# COMMUNICATION.net
KiCad netlist of a schematic drawn in Altium Designer
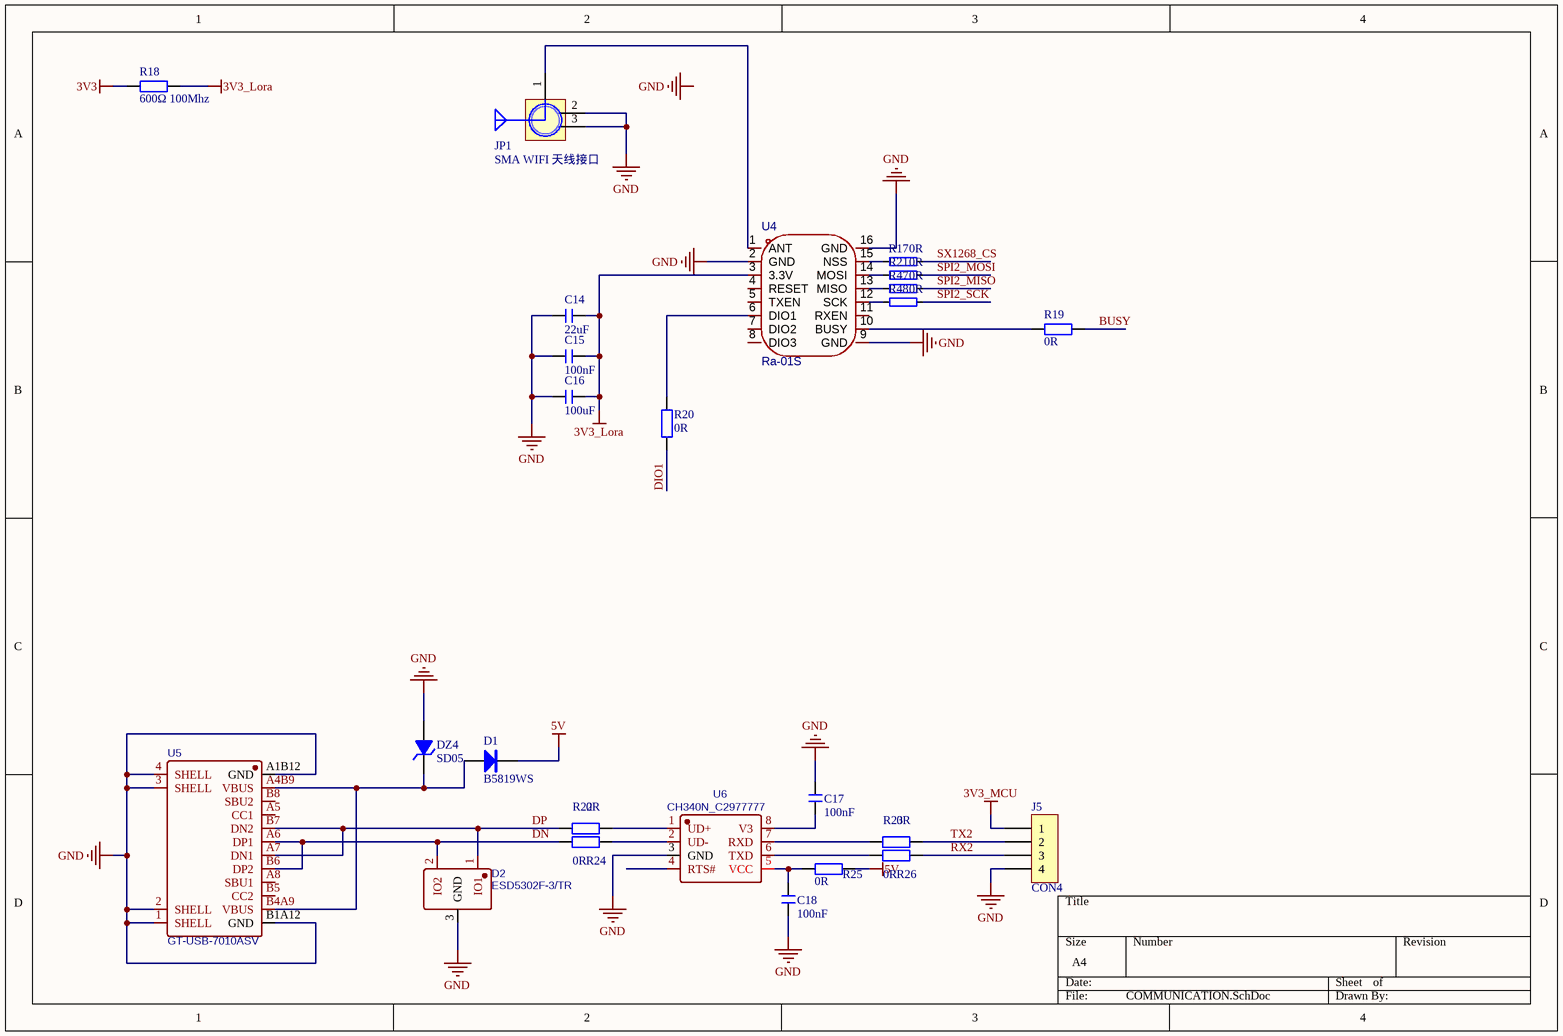
[diagram p0: COMMUNICATION.SchDoc]

(export (version "E")
  (design (tool "Eeschema 10.0.6"))
  (components
    (comp (ref "C14")
      (value "22uF")
      (footprint "C 0805_L")
      (description "无极性贴片电容")
      (fields (field (name "版权归属") "源创客"))
      (libsource (lib "3.1   - 电阻-电容-电感") (part "C"))
    )
    (comp (ref "C15")
      (value "100nF")
      (footprint "C 0603_L")
      (description "无极性贴片电容")
      (fields (field (name "版权归属") "源创客"))
      (libsource (lib "3.1   - 电阻-电容-电感") (part "C"))
    )
    (comp (ref "C16")
      (value "100uF")
      (footprint "C 0603_L")
      (description "无极性贴片电容")
      (fields (field (name "版权归属") "源创客"))
      (libsource (lib "3.1   - 电阻-电容-电感") (part "C"))
    )
    (comp (ref "C17")
      (value "100nF")
      (footprint "C 0603_L")
      (description "无极性贴片电容")
      (fields (field (name "版权归属") "源创客"))
      (libsource (lib "3.1   - 电阻-电容-电感") (part "C"))
    )
    (comp (ref "C18")
      (value "100nF")
      (footprint "C 0603_L")
      (description "无极性贴片电容")
      (fields (field (name "版权归属") "源创客"))
      (libsource (lib "3.1   - 电阻-电容-电感") (part "C"))
    )
    (comp (ref "D1")
      (value "B5819WS")
      (footprint "SOD-323")
      (description "肖特基二极管                           电压:40V 电流:1A                 C7420331")
      (fields (field (name "版权归属") "源创客"))
      (libsource (lib "8.1   - 二极管-整流桥") (part "SR540"))
    )
    (comp (ref "D2")
      (value "ESD5302F-3/TR")
      (footprint "SOT-23")
      (description "单向TVS 5V截止 峰值浪涌电流：4A@8/20us                        C239643")
      (fields (field (name "MANUFACTURER") "WILLSEMI(韦尔)") (field (name "CONTRIBUTOR") "LCSC"))
      (libsource (lib "altium-import") (part "root_2_ESD5302F-3/TR_"))
    )
    (comp (ref "DZ4")
      (value "SD05")
      (footprint "SOD-323")
      (description "单向TVS 5V截止 峰值脉冲电流：17A              C502527")
      (fields (field (name "版权归属") "源创客"))
      (libsource (lib "8.1   - 二极管-整流桥") (part "1N4106"))
    )
    (comp (ref "J5")
      (value "CON4")
      (footprint "HDR2.54-LI-4P")
      (description "Connector")
      (libsource (lib "插件") (part "CON4"))
    )
    (comp (ref "JP1")
      (value "SMA WIFI 天线接口")
      (footprint "SMA-KE")
      (description "SMA-2.4G射频天线接口")
      (fields (field (name "版权归属") "源创客"))
      (libsource (lib "14.1 - 天线") (part "SMA"))
    )
    (comp (ref "R17") (value "0R") (footprint "R 0603_L") (libsource (lib "电阻电容电感") (part "普通电阻")))
    (comp (ref "R18")
      (value "600Ω 100Mhz")
      (footprint "R 0805_L")
      (description "磁珠")
      (fields (field (name "版权归属") "源创客"))
      (libsource (lib "3.1   - 电阻-电容-电感") (part "R"))
    )
    (comp (ref "R19")
      (value "0R")
      (footprint "R 0603_L")
      (description "贴片电阻")
      (fields (field (name "版权归属") "源创客"))
      (libsource (lib "3.1   - 电阻-电容-电感") (part "R"))
    )
    (comp (ref "R20")
      (value "0R")
      (footprint "R 0603_L")
      (description "贴片电阻")
      (fields (field (name "版权归属") "源创客"))
      (libsource (lib "3.1   - 电阻-电容-电感") (part "R"))
    )
    (comp (ref "R21") (value "0R") (footprint "R 0603_L") (libsource (lib "电阻电容电感") (part "普通电阻")))
    (comp (ref "R22")
      (value "0R")
      (footprint "R 0603_L")
      (description "贴片电阻")
      (fields (field (name "版权归属") "源创客"))
      (libsource (lib "3.1   - 电阻-电容-电感") (part "R"))
    )
    (comp (ref "R23")
      (value "0R")
      (footprint "R 0603_L")
      (description "贴片电阻")
      (fields (field (name "版权归属") "源创客"))
      (libsource (lib "3.1   - 电阻-电容-电感") (part "R"))
    )
    (comp (ref "R24")
      (value "0R")
      (footprint "R 0603_L")
      (description "贴片电阻")
      (fields (field (name "版权归属") "源创客"))
      (libsource (lib "3.1   - 电阻-电容-电感") (part "R"))
    )
    (comp (ref "R25")
      (value "0R")
      (footprint "R 0603_L")
      (description "贴片电阻")
      (fields (field (name "版权归属") "源创客"))
      (libsource (lib "3.1   - 电阻-电容-电感") (part "R"))
    )
    (comp (ref "R26")
      (value "0R")
      (footprint "R 0603_L")
      (description "贴片电阻")
      (fields (field (name "版权归属") "源创客"))
      (libsource (lib "3.1   - 电阻-电容-电感") (part "R"))
    )
    (comp (ref "R47") (value "0R") (footprint "R 0603_L") (libsource (lib "电阻电容电感") (part "普通电阻")))
    (comp (ref "R48") (value "0R") (footprint "R 0603_L") (libsource (lib "电阻电容电感") (part "普通电阻")))
    (comp (ref "U4")
      (value "Ra-01S")
      (footprint "RA-01SCH-P-TJFZ")
      (description "发射功率:22dBm;接口类型:SPI;接收灵敏度:-140dBm;")
      (fields (field (name "MANUFACTURER") "Ai-Thinker(安信可)"))
      (libsource (lib "altium-import") (part "root_0_Ra-01S_"))
    )
    (comp (ref "U5")
      (value "GT-USB-7010ASV")
      (footprint "USB-C-SMD_G-SWITCH_GT-USB-7010ASV")
      (description "Type-C 母 卧贴                板上16pin，有柱无弹，L7.35 CH1.68mm，3A电流                         C2988369")
      (fields (field (name "MANUFACTURER") "G-Switch(品赞)") (field (name "CONTRIBUTOR") "lcsc"))
      (libsource (lib "altium-import") (part "root_0_mirrored_GT-USB-7010ASV_"))
    )
    (comp (ref "U6")
      (value "CH340N_C2977777")
      (footprint "SOP8")
      (fields
        (field (name "MANUFACTURER") "WCH(南京沁恒)")
        (field (name "MANUFACTURER PART") "CH340N")
        (field (name "CONTRIBUTOR") "LCSC")
      )
      (libsource (lib "altium-import") (part "root_0_CH340N_C2977777_"))
    )
  )
  (nets
    (net (code "1") (name "/BUSY") (class "Default")
      (node (ref "R19") (pin "1") (pinfunction "1_1") (pintype "passive"))
    )
    (net (code "2") (name "/DIO1") (class "Default")
      (node (ref "R20") (pin "1") (pinfunction "1_1") (pintype "passive"))
    )
    (net (code "3") (name "/DN") (class "Default")
      (node (ref "D2") (pin "2") (pinfunction "IO2_2") (pintype "passive"))
      (node (ref "R24") (pin "1") (pinfunction "1_1") (pintype "passive"))
      (node (ref "U5") (pin "A6") (pinfunction "DP1_A6") (pintype "passive"))
      (node (ref "U5") (pin "B6") (pinfunction "DP2_B6") (pintype "passive"))
    )
    (net (code "4") (name "/DP") (class "Default")
      (node (ref "D2") (pin "1") (pinfunction "IO1_1") (pintype "passive"))
      (node (ref "R22") (pin "1") (pinfunction "1_1") (pintype "passive"))
      (node (ref "U5") (pin "A7") (pinfunction "DN1_A7") (pintype "passive"))
      (node (ref "U5") (pin "B7") (pinfunction "DN2_B7") (pintype "passive"))
    )
    (net (code "5") (name "/RX2") (class "Default")
      (node (ref "J5") (pin "3") (pinfunction "3_3") (pintype "passive"))
      (node (ref "R26") (pin "2") (pinfunction "2_2") (pintype "passive"))
    )
    (net (code "6") (name "/SPI2_MISO") (class "Default")
      (node (ref "R47") (pin "1") (pinfunction "1_1") (pintype "passive"))
    )
    (net (code "7") (name "/SPI2_MOSI") (class "Default")
      (node (ref "R21") (pin "1") (pinfunction "1_1") (pintype "passive"))
    )
    (net (code "8") (name "/SPI2_SCK") (class "Default")
      (node (ref "R48") (pin "1") (pinfunction "1_1") (pintype "passive"))
    )
    (net (code "9") (name "/SX1268_CS") (class "Default")
      (node (ref "R17") (pin "1") (pinfunction "1_1") (pintype "passive"))
    )
    (net (code "10") (name "/TX2") (class "Default")
      (node (ref "J5") (pin "2") (pinfunction "2_2") (pintype "passive"))
      (node (ref "R23") (pin "2") (pinfunction "2_2") (pintype "passive"))
    )
    (net (code "11") (name "3V3") (class "Default")
      (node (ref "R18") (pin "1") (pinfunction "1_1") (pintype "passive"))
    )
    (net (code "12") (name "3V3_Lora") (class "Default")
      (node (ref "C14") (pin "2") (pinfunction "2_2") (pintype "passive"))
      (node (ref "C15") (pin "2") (pinfunction "2_2") (pintype "passive"))
      (node (ref "C16") (pin "2") (pinfunction "2_2") (pintype "passive"))
      (node (ref "R18") (pin "2") (pinfunction "2_2") (pintype "passive"))
      (node (ref "U4") (pin "3") (pinfunction "3.3V_3") (pintype "passive"))
    )
    (net (code "13") (name "3V3_MCU") (class "Default")
      (node (ref "J5") (pin "1") (pinfunction "1_1") (pintype "passive"))
    )
    (net (code "14") (name "5V") (class "Default")
      (node (ref "D1") (pin "2") (pinfunction "K_2") (pintype "passive"))
      (node (ref "R25") (pin "2") (pinfunction "2_2") (pintype "passive"))
    )
    (net (code "15") (name "GND") (class "Default")
      (node (ref "C14") (pin "1") (pinfunction "1_1") (pintype "passive"))
      (node (ref "C15") (pin "1") (pinfunction "1_1") (pintype "passive"))
      (node (ref "C16") (pin "1") (pinfunction "1_1") (pintype "passive"))
      (node (ref "C17") (pin "1") (pinfunction "1_1") (pintype "passive"))
      (node (ref "C18") (pin "2") (pinfunction "2_2") (pintype "passive"))
      (node (ref "D2") (pin "3") (pinfunction "GND_3") (pintype "passive"))
      (node (ref "DZ4") (pin "1") (pinfunction "A_1") (pintype "passive"))
      (node (ref "J5") (pin "4") (pinfunction "4_4") (pintype "passive"))
      (node (ref "JP1") (pin "2") (pinfunction "GND_2") (pintype "passive"))
      (node (ref "JP1") (pin "3") (pinfunction "GND_3") (pintype "passive"))
      (node (ref "U4") (pin "16") (pinfunction "GND_16") (pintype "passive"))
      (node (ref "U4") (pin "2") (pinfunction "GND_2") (pintype "passive"))
      (node (ref "U4") (pin "9") (pinfunction "GND_9") (pintype "passive"))
      (node (ref "U5") (pin "1") (pinfunction "SHELL_1") (pintype "passive"))
      (node (ref "U5") (pin "2") (pinfunction "SHELL_2") (pintype "passive"))
      (node (ref "U5") (pin "3") (pinfunction "SHELL_3") (pintype "passive"))
      (node (ref "U5") (pin "4") (pinfunction "SHELL_4") (pintype "passive"))
      (node (ref "U5") (pin "A1B12") (pinfunction "GND_A1B12") (pintype "passive"))
      (node (ref "U5") (pin "B1A12") (pinfunction "GND_B1A12") (pintype "passive"))
      (node (ref "U6") (pin "3") (pinfunction "GND_3") (pintype "passive"))
    )
    (net (code "16") (name "Net-(D1-A)") (class "Default")
      (node (ref "D1") (pin "1") (pinfunction "A_1") (pintype "passive"))
      (node (ref "DZ4") (pin "2") (pinfunction "K_2") (pintype "passive"))
      (node (ref "U5") (pin "A4B9") (pinfunction "VBUS_A4B9") (pintype "passive"))
      (node (ref "U5") (pin "B4A9") (pinfunction "VBUS_B4A9") (pintype "passive"))
    )
    (net (code "17") (name "Net-(JP1-ANT)") (class "Default")
      (node (ref "JP1") (pin "1") (pinfunction "ANT_1") (pintype "passive"))
      (node (ref "U4") (pin "1") (pinfunction "ANT_1") (pintype "passive"))
    )
    (net (code "18") (name "Net-(U4-BUSY)") (class "Default")
      (node (ref "R19") (pin "2") (pinfunction "2_2") (pintype "passive"))
      (node (ref "U4") (pin "10") (pinfunction "BUSY_10") (pintype "passive"))
    )
    (net (code "19") (name "Net-(U4-DIO1)") (class "Default")
      (node (ref "R20") (pin "2") (pinfunction "2_2") (pintype "passive"))
      (node (ref "U4") (pin "6") (pinfunction "DIO1_6") (pintype "passive"))
    )
    (net (code "20") (name "Net-(U4-MISO)") (class "Default")
      (node (ref "R47") (pin "2") (pinfunction "2_2") (pintype "passive"))
      (node (ref "U4") (pin "13") (pinfunction "MISO_13") (pintype "passive"))
    )
    (net (code "21") (name "Net-(U4-MOSI)") (class "Default")
      (node (ref "R21") (pin "2") (pinfunction "2_2") (pintype "passive"))
      (node (ref "U4") (pin "14") (pinfunction "MOSI_14") (pintype "passive"))
    )
    (net (code "22") (name "Net-(U4-NSS)") (class "Default")
      (node (ref "R17") (pin "2") (pinfunction "2_2") (pintype "passive"))
      (node (ref "U4") (pin "15") (pinfunction "NSS_15") (pintype "passive"))
    )
    (net (code "23") (name "Net-(U4-SCK)") (class "Default")
      (node (ref "R48") (pin "2") (pinfunction "2_2") (pintype "passive"))
      (node (ref "U4") (pin "12") (pinfunction "SCK_12") (pintype "passive"))
    )
    (net (code "24") (name "Net-(U6-RXD)") (class "Default")
      (node (ref "R23") (pin "1") (pinfunction "1_1") (pintype "passive"))
      (node (ref "U6") (pin "7") (pinfunction "RXD_7") (pintype "passive"))
    )
    (net (code "25") (name "Net-(U6-TXD)") (class "Default")
      (node (ref "R26") (pin "1") (pinfunction "1_1") (pintype "passive"))
      (node (ref "U6") (pin "6") (pinfunction "TXD_6") (pintype "passive"))
    )
    (net (code "26") (name "Net-(U6-UD+)") (class "Default")
      (node (ref "R22") (pin "2") (pinfunction "2_2") (pintype "passive"))
      (node (ref "U6") (pin "1") (pinfunction "UD+_1") (pintype "passive"))
    )
    (net (code "27") (name "Net-(U6-UD-)") (class "Default")
      (node (ref "R24") (pin "2") (pinfunction "2_2") (pintype "passive"))
      (node (ref "U6") (pin "2") (pinfunction "UD-_2") (pintype "passive"))
    )
    (net (code "28") (name "Net-(U6-V3)") (class "Default")
      (node (ref "C17") (pin "2") (pinfunction "2_2") (pintype "passive"))
      (node (ref "U6") (pin "8") (pinfunction "V3_8") (pintype "passive"))
    )
    (net (code "29") (name "Net-(U6-VCC)") (class "Default")
      (node (ref "C18") (pin "1") (pinfunction "1_1") (pintype "passive"))
      (node (ref "R25") (pin "1") (pinfunction "1_1") (pintype "passive"))
      (node (ref "U6") (pin "5") (pinfunction "VCC_5") (pintype "passive"))
    )
    (net (code "30") (name "unconnected-(U4-DIO2-Pad7)") (class "Default")
      (node (ref "U4") (pin "7") (pinfunction "DIO2_7") (pintype "passive"))
    )
    (net (code "31") (name "unconnected-(U4-DIO3-Pad8)") (class "Default")
      (node (ref "U4") (pin "8") (pinfunction "DIO3_8") (pintype "passive"))
    )
    (net (code "32") (name "unconnected-(U4-RESET-Pad4)") (class "Default")
      (node (ref "U4") (pin "4") (pinfunction "RESET_4") (pintype "passive"))
    )
    (net (code "33") (name "unconnected-(U4-RXEN-Pad11)") (class "Default")
      (node (ref "U4") (pin "11") (pinfunction "RXEN_11") (pintype "passive"))
    )
    (net (code "34") (name "unconnected-(U4-TXEN-Pad5)") (class "Default")
      (node (ref "U4") (pin "5") (pinfunction "TXEN_5") (pintype "passive"))
    )
    (net (code "35") (name "unconnected-(U5-CC1-PadA5)") (class "Default")
      (node (ref "U5") (pin "A5") (pinfunction "CC1_A5") (pintype "passive"))
    )
    (net (code "36") (name "unconnected-(U5-CC2-PadB5)") (class "Default")
      (node (ref "U5") (pin "B5") (pinfunction "CC2_B5") (pintype "passive"))
    )
    (net (code "37") (name "unconnected-(U5-SBU1-PadA8)") (class "Default")
      (node (ref "U5") (pin "A8") (pinfunction "SBU1_A8") (pintype "passive"))
    )
    (net (code "38") (name "unconnected-(U5-SBU2-PadB8)") (class "Default")
      (node (ref "U5") (pin "B8") (pinfunction "SBU2_B8") (pintype "passive"))
    )
    (net (code "39") (name "unconnected-(U6-RTS#-Pad4)") (class "Default")
      (node (ref "U6") (pin "4") (pinfunction "RTS#_4") (pintype "passive"))
    )
  )
)
